# Sheet1.net
KiCad netlist of a schematic drawn in Altium Designer
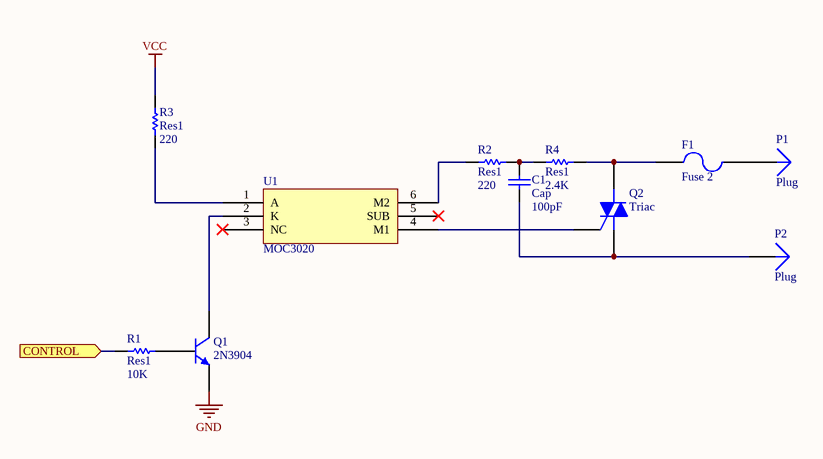
[diagram p0: Sheet1.SchDoc]

(export (version "E")
  (design (tool "Eeschema 10.0.6"))
  (components
    (comp (ref "C1")
      (value "Cap")
      (footprint "RAD-0.3")
      (description "Capacitor")
      (fields (field (name "ALTIUM_VALUE") "100pF") (field (name "PUBLISHER") "Altium Limited"))
      (libsource (lib "Miscellaneous Devices") (part "Cap"))
    )
    (comp (ref "F1")
      (value "Fuse 2")
      (footprint "PIN-W2/E2.8")
      (description "Fuse")
      (fields (field (name "PUBLISHER") "Altium Limited"))
      (libsource (lib "Miscellaneous Devices") (part "Fuse 2"))
    )
    (comp (ref "P1")
      (value "Plug")
      (footprint "PIN1")
      (fields (field (name "PUBLISHER") "Altium Limited"))
      (libsource (lib "Miscellaneous Connectors") (part "Plug"))
    )
    (comp (ref "P2")
      (value "Plug")
      (footprint "PIN1")
      (fields (field (name "PUBLISHER") "Altium Limited"))
      (libsource (lib "Miscellaneous Connectors") (part "Plug"))
    )
    (comp (ref "Q1")
      (value "2N3904")
      (footprint "TO-92A")
      (description "NPN General Purpose Amplifier")
      (fields (field (name "PUBLISHER") "Altium Limited"))
      (libsource (lib "Miscellaneous Devices") (part "2N3904"))
    )
    (comp (ref "Q2")
      (value "Triac")
      (footprint "369-03")
      (description "Silicon Bidirectional Triode Thyristor")
      (fields (field (name "PUBLISHER") "Altium Limited"))
      (libsource (lib "Miscellaneous Devices") (part "Triac"))
    )
    (comp (ref "R1")
      (value "Res1")
      (footprint "AXIAL-0.3")
      (description "Resistor")
      (fields (field (name "ALTIUM_VALUE") "10K") (field (name "PUBLISHER") "Altium Limited"))
      (libsource (lib "Miscellaneous Devices") (part "Res1"))
    )
    (comp (ref "R2")
      (value "Res1")
      (footprint "AXIAL-0.3")
      (description "Resistor")
      (fields (field (name "ALTIUM_VALUE") "220") (field (name "PUBLISHER") "Altium Limited"))
      (libsource (lib "Miscellaneous Devices") (part "Res1"))
    )
    (comp (ref "R3")
      (value "Res1")
      (footprint "AXIAL-0.3")
      (description "Resistor")
      (fields (field (name "ALTIUM_VALUE") "220") (field (name "PUBLISHER") "Altium Limited"))
      (libsource (lib "Miscellaneous Devices") (part "Res1"))
    )
    (comp (ref "R4")
      (value "Res1")
      (footprint "AXIAL-0.3")
      (description "Resistor")
      (fields (field (name "ALTIUM_VALUE") "2.4K") (field (name "PUBLISHER") "Altium Limited"))
      (libsource (lib "Miscellaneous Devices") (part "Res1"))
    )
    (comp (ref "U1")
      (value "MOC3020")
      (footprint "MOC3020 - duplicate")
      (libsource (lib "MOC3020") (part "Component_1"))
    )
  )
  (nets
    (net (code "1") (name "/CONTROL") (class "Default")
      (node (ref "R1") (pin "2") (pinfunction "2_2") (pintype "passive"))
    )
    (net (code "2") (name "GND") (class "Default")
      (node (ref "Q1") (pin "1") (pinfunction "E_1") (pintype "passive"))
    )
    (net (code "3") (name "Net-(C1-Pad2)") (class "Default")
      (node (ref "C1") (pin "2") (pinfunction "2_2") (pintype "passive"))
      (node (ref "R2") (pin "2") (pinfunction "2_2") (pintype "passive"))
      (node (ref "R4") (pin "1") (pinfunction "1_1") (pintype "passive"))
    )
    (net (code "4") (name "Net-(F1-Pad2)") (class "Default")
      (node (ref "F1") (pin "2") (pinfunction "2_2") (pintype "passive"))
      (node (ref "P1") (pin "1") (pinfunction "1_1") (pintype "passive"))
    )
    (net (code "5") (name "Net-(Q1-B)") (class "Default")
      (node (ref "Q1") (pin "2") (pinfunction "B_2") (pintype "passive"))
      (node (ref "R1") (pin "1") (pinfunction "1_1") (pintype "passive"))
    )
    (net (code "6") (name "Net-(Q1-C)") (class "Default")
      (node (ref "Q1") (pin "3") (pinfunction "C_3") (pintype "passive"))
      (node (ref "U1") (pin "2") (pinfunction "K_2") (pintype "passive"))
    )
    (net (code "7") (name "Net-(Q2-G)") (class "Default")
      (node (ref "Q2") (pin "3") (pinfunction "G_3") (pintype "passive"))
      (node (ref "U1") (pin "4") (pinfunction "M1_4") (pintype "passive"))
    )
    (net (code "8") (name "Net-(Q2-M1)") (class "Default")
      (node (ref "C1") (pin "1") (pinfunction "1_1") (pintype "passive"))
      (node (ref "P2") (pin "1") (pinfunction "1_1") (pintype "passive"))
      (node (ref "Q2") (pin "1") (pinfunction "M1_1") (pintype "passive"))
    )
    (net (code "9") (name "Net-(Q2-M2)") (class "Default")
      (node (ref "F1") (pin "1") (pinfunction "1_1") (pintype "passive"))
      (node (ref "Q2") (pin "2") (pinfunction "M2_2") (pintype "passive"))
      (node (ref "R4") (pin "2") (pinfunction "2_2") (pintype "passive"))
    )
    (net (code "10") (name "Net-(U1-A)") (class "Default")
      (node (ref "R3") (pin "1") (pinfunction "1_1") (pintype "passive"))
      (node (ref "U1") (pin "1") (pinfunction "A_1") (pintype "passive"))
    )
    (net (code "11") (name "Net-(U1-M2)") (class "Default")
      (node (ref "R2") (pin "1") (pinfunction "1_1") (pintype "passive"))
      (node (ref "U1") (pin "6") (pinfunction "M2_6") (pintype "passive"))
    )
    (net (code "12") (name "VCC") (class "Default")
      (node (ref "R3") (pin "2") (pinfunction "2_2") (pintype "passive"))
    )
    (net (code "13") (name "unconnected-(U1-NC-Pad3)") (class "Default")
      (node (ref "U1") (pin "3") (pinfunction "NC_3") (pintype "passive+no_connect"))
    )
    (net (code "14") (name "unconnected-(U1-SUB-Pad5)") (class "Default")
      (node (ref "U1") (pin "5") (pinfunction "SUB_5") (pintype "passive+no_connect"))
    )
  )
)
